# zulu_a7_1.net
KiCad netlist of a schematic drawn in Altium Designer
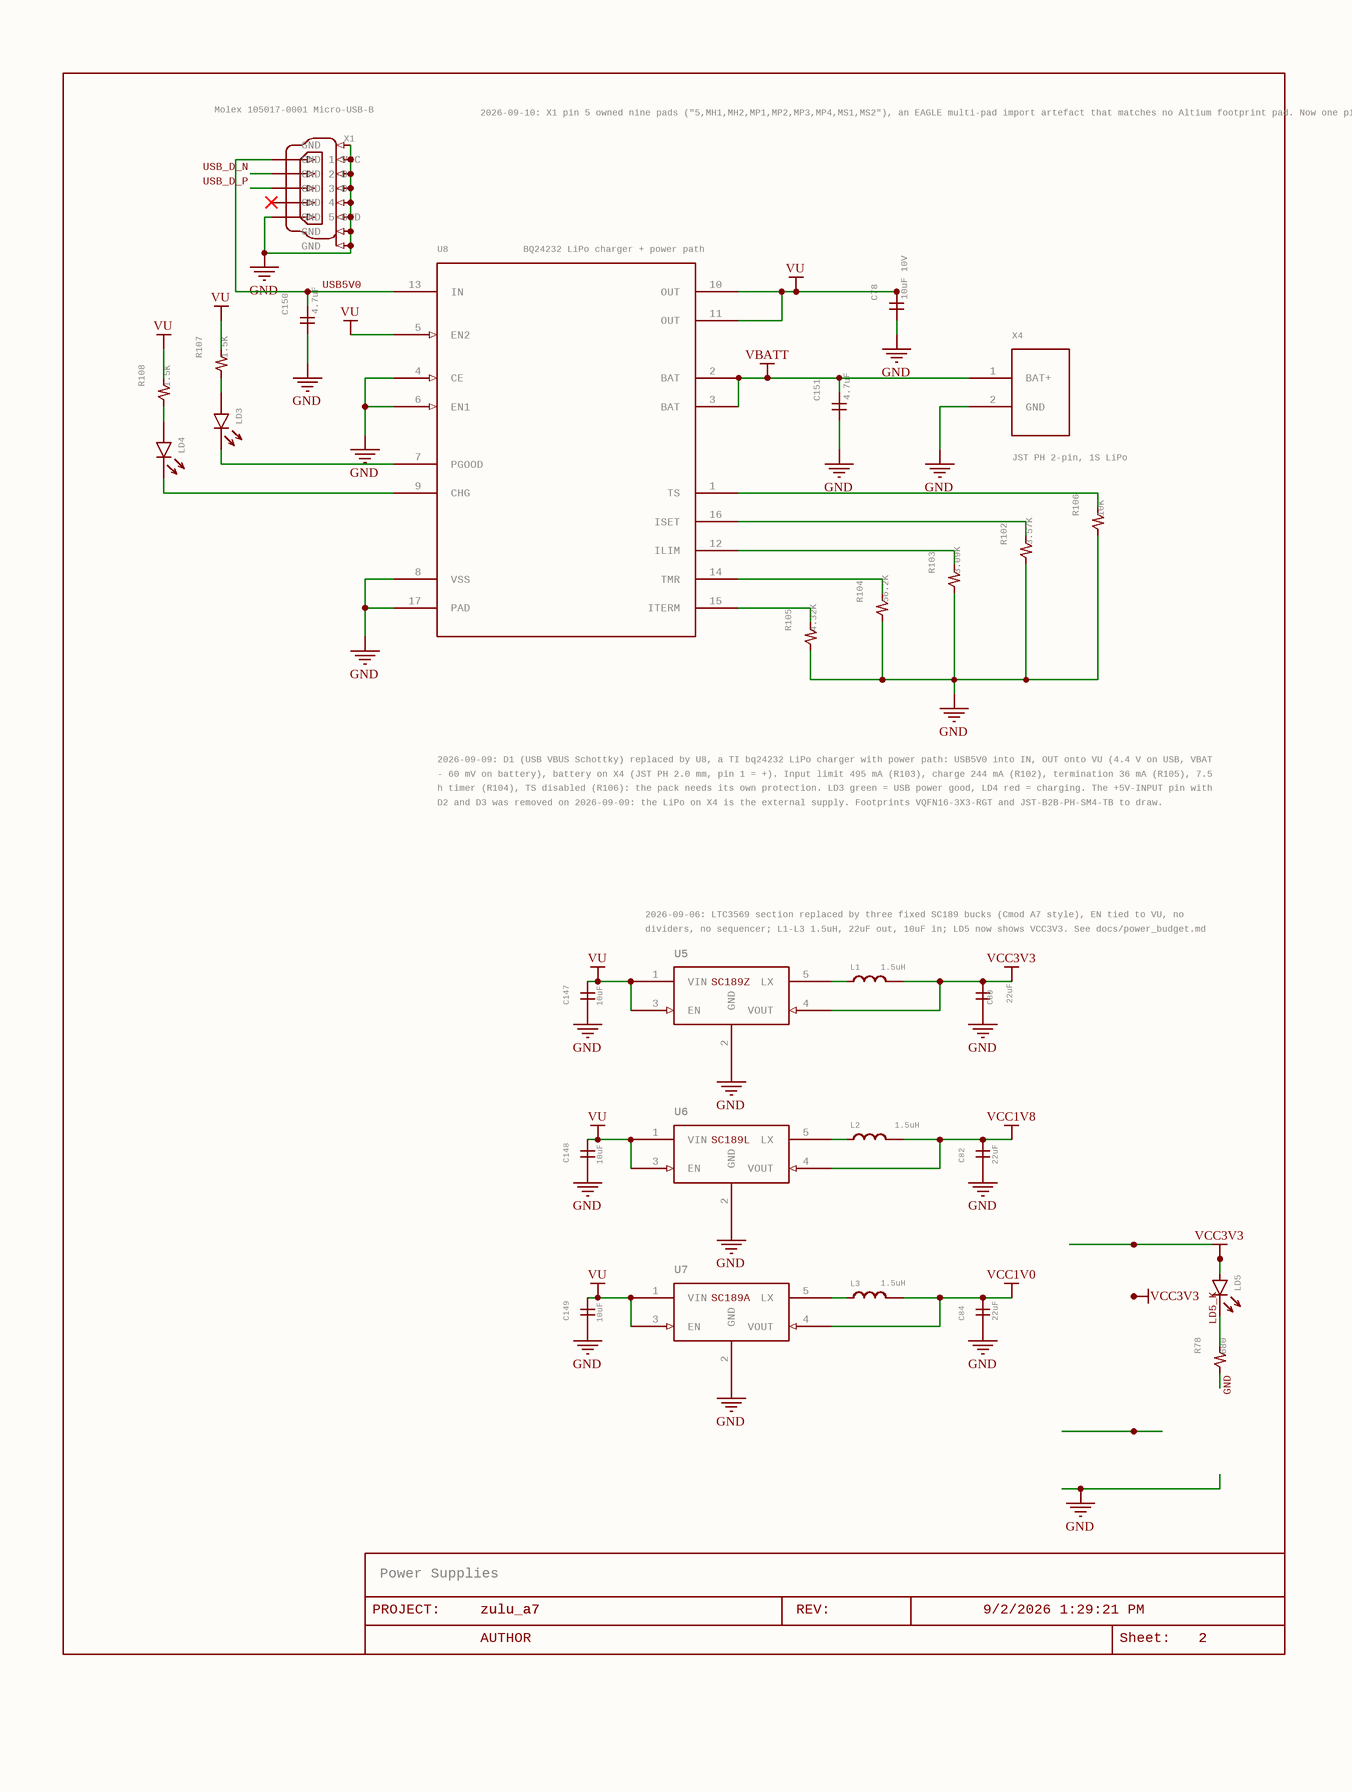
[diagram p0: zulu_a7_1.SchDoc]

(export (version "E")
  (design (tool "Eeschema 10.0.6"))
  (components
    (comp (ref "C78")
      (value "10uF 10V")
      (footprint "C0805")
      (description "CAPACITOR, generic non-polarized, horizontal pins")
      (fields (field (name "MANF") "Samsung"))
      (libsource (lib "rcl") (part "C-GENERICC0805"))
    )
    (comp (ref "C80")
      (value "22uF")
      (footprint "C0805")
      (description "CAPACITOR, generic non-polarized, horizontal pins")
      (fields (field (name "MANF") "Murata"))
      (libsource (lib "rcl") (part "C-GENERICC0805"))
    )
    (comp (ref "C82")
      (value "22uF")
      (footprint "C0603")
      (description "CAPACITOR, generic non-polarized, horizontal pins")
      (fields (field (name "MANF") "Samsung"))
      (libsource (lib "rcl") (part "C-GENERICC0603"))
    )
    (comp (ref "C84")
      (value "22uF")
      (footprint "C0603")
      (description "CAPACITOR, generic non-polarized, horizontal pins")
      (fields (field (name "MANF") "Samsung"))
      (libsource (lib "rcl") (part "C-GENERICC0603"))
    )
    (comp (ref "C147")
      (value "10uF")
      (footprint "C0805")
      (description "CAPACITOR, generic non-polarized, horizontal pins")
      (fields (field (name "MANF") "Samsung"))
      (libsource (lib "rcl") (part "C-GENERICC0805"))
    )
    (comp (ref "C148")
      (value "10uF")
      (footprint "C0805")
      (description "CAPACITOR, generic non-polarized, horizontal pins")
      (fields (field (name "MANF") "Samsung"))
      (libsource (lib "rcl") (part "C-GENERICC0805"))
    )
    (comp (ref "C149")
      (value "10uF")
      (footprint "C0805")
      (description "CAPACITOR, generic non-polarized, horizontal pins")
      (fields (field (name "MANF") "Samsung"))
      (libsource (lib "rcl") (part "C-GENERICC0805"))
    )
    (comp (ref "C150")
      (value "4.7uF")
      (footprint "C0603")
      (description "CAPACITOR, generic non-polarized, horizontal pins")
      (fields (field (name "MANF") "Murata"))
      (libsource (lib "rcl") (part "C-GENERICC0603"))
    )
    (comp (ref "C151")
      (value "4.7uF")
      (footprint "C0603")
      (description "CAPACITOR, generic non-polarized, horizontal pins")
      (fields (field (name "MANF") "Murata"))
      (libsource (lib "rcl") (part "C-GENERICC0603"))
    )
    (comp (ref "FRAME5")
      (value "DOCFIELD")
      (description "DOCUMENT FIELD")
      (fields
        (field (name "LAST_DATE_TIME") "9/2/2026 1:29:21 PM")
        (field (name "SHEET") "Sheet:")
        (field (name "SHEET_1") "2")
        (field (name "REV") "REV:")
        (field (name "PROJECT") "PROJECT:")
        (field (name "DRAWING_NAME") "zulu_a7")
        (field (name "AUTHOR") "AUTHOR")
        (field (name "DRAWING_NAME_1") "zulu_a7")
        (field (name "SHEET_2") "2")
        (field (name "LIBRARYNAME") "ctambe")
      )
      (libsource (lib "ctambe") (part "DOCFIELD"))
    )
    (comp (ref "L1")
      (value "1.5uH")
      (footprint "IND2520")
      (description "INDUCTOR, generic power inductor")
      (fields (field (name "MANF") "Murata") (field (name "LIBRARYNAME") "ctambe"))
      (libsource (lib "ctambe") (part "INDUCTOR-2520"))
    )
    (comp (ref "L2")
      (value "1.5uH")
      (footprint "IND2520")
      (description "INDUCTOR, generic power inductor")
      (fields (field (name "MANF") "Murata") (field (name "LIBRARYNAME") "ctambe"))
      (libsource (lib "ctambe") (part "INDUCTOR-2520"))
    )
    (comp (ref "L3")
      (value "1.5uH")
      (footprint "IND2520")
      (description "INDUCTOR, generic power inductor")
      (fields (field (name "MANF") "Murata") (field (name "LIBRARYNAME") "ctambe"))
      (libsource (lib "ctambe") (part "INDUCTOR-2520"))
    )
    (comp (ref "LD3")
      (value "green")
      (footprint "LED0603")
      (description "LED")
      (fields (field (name "MANF") "Lite-On") (field (name "LIBRARYNAME") "ctambe"))
      (libsource (lib "ctambe") (part "LED"))
    )
    (comp (ref "LD4")
      (value "red")
      (footprint "LED0603")
      (description "LED")
      (fields (field (name "MANF") "Lite-On") (field (name "LIBRARYNAME") "ctambe"))
      (libsource (lib "ctambe") (part "LED"))
    )
    (comp (ref "LD5")
      (value "green")
      (footprint "LED0603")
      (description "LED")
      (fields (field (name "MANF") "Lite-On") (field (name "LIBRARYNAME") "ctambe"))
      (libsource (lib "ctambe") (part "LED"))
    )
    (comp (ref "R78")
      (value "680")
      (footprint "R0402")
      (description "RESISTOR, American symbol, small 2-zigzag variant (sheet 2 only)")
      (fields (field (name "MANF") "Yageo"))
      (libsource (lib "rcl") (part "R-US_SMALLR0402"))
    )
    (comp (ref "R102")
      (value "3.57K")
      (footprint "R0402")
      (description "RESISTOR, American symbol, small 2-zigzag variant (sheet 2 only)")
      (fields (field (name "MANF") "Yageo"))
      (libsource (lib "rcl") (part "R-US_SMALLR0402"))
    )
    (comp (ref "R103")
      (value "3.09K")
      (footprint "R0402")
      (description "RESISTOR, American symbol, small 2-zigzag variant (sheet 2 only)")
      (fields (field (name "MANF") "Yageo"))
      (libsource (lib "rcl") (part "R-US_SMALLR0402"))
    )
    (comp (ref "R104")
      (value "56.2K")
      (footprint "R0402")
      (description "RESISTOR, American symbol, small 2-zigzag variant (sheet 2 only)")
      (fields (field (name "MANF") "Yageo"))
      (libsource (lib "rcl") (part "R-US_SMALLR0402"))
    )
    (comp (ref "R105")
      (value "4.32K")
      (footprint "R0402")
      (description "RESISTOR, American symbol, small 2-zigzag variant (sheet 2 only)")
      (fields (field (name "MANF") "Yageo"))
      (libsource (lib "rcl") (part "R-US_SMALLR0402"))
    )
    (comp (ref "R106")
      (value "10K")
      (footprint "R0402")
      (description "RESISTOR, American symbol, small 2-zigzag variant (sheet 2 only)")
      (fields (field (name "MANF") "Yageo"))
      (libsource (lib "rcl") (part "R-US_SMALLR0402"))
    )
    (comp (ref "R107")
      (value "1.5K")
      (footprint "R0402")
      (description "RESISTOR, American symbol, small 2-zigzag variant (sheet 2 only)")
      (fields (field (name "MANF") "Yageo"))
      (libsource (lib "rcl") (part "R-US_SMALLR0402"))
    )
    (comp (ref "R108")
      (value "1.5K")
      (footprint "R0402")
      (description "RESISTOR, American symbol, small 2-zigzag variant (sheet 2 only)")
      (fields (field (name "MANF") "Yageo"))
      (libsource (lib "rcl") (part "R-US_SMALLR0402"))
    )
    (comp (ref "U5")
      (value "SC189ZSKTRT")
      (footprint "SOT23-5")
      (description "1.5A 2.5MHz synchronous buck, fixed output (Semtech SC189)")
      (fields (field (name "PARTNAME") "SC189Z") (field (name "MANF") "Semtech"))
      (libsource (lib "ctambe") (part "SC189-SOT23-5"))
    )
    (comp (ref "U6")
      (value "SC189LSKTRT")
      (footprint "SOT23-5")
      (description "1.5A 2.5MHz synchronous buck, fixed output (Semtech SC189)")
      (fields (field (name "PARTNAME") "SC189L") (field (name "MANF") "Semtech"))
      (libsource (lib "ctambe") (part "SC189-SOT23-5"))
    )
    (comp (ref "U7")
      (value "SC189ASKTRT")
      (footprint "SOT23-5")
      (description "1.5A 2.5MHz synchronous buck, fixed output (Semtech SC189)")
      (fields (field (name "PARTNAME") "SC189A") (field (name "MANF") "Semtech"))
      (libsource (lib "ctambe") (part "SC189-SOT23-5"))
    )
    (comp (ref "U8")
      (value "BQ24232 LiPo charger + power path")
      (footprint "VQFN16-3X3-RGT")
      (fields (field (name "MANF") "Texas Instruments") (field (name "LIBRARYNAME") "ctambe"))
      (libsource (lib "ctambe") (part "BQ24232-RGT16"))
    )
    (comp (ref "X1")
      (value "Molex 105017-0001 Micro-USB-B")
      (footprint "MOLEX-105017-0001")
      (description "MINI USB Connector   Source: http://www.hirose.co.jp/cataloge_hp/e24000019.pdf")
      (fields (field (name "MANF") "Molex") (field (name "LIBRARYNAME") "ctambe"))
      (libsource (lib "ctambe") (part "MINI-USB-105017-0001"))
    )
    (comp (ref "X4")
      (value "JST PH 2-pin, 1S LiPo")
      (footprint "JST-B2B-PH-SM4-TB")
      (description "JST PH 2.0 mm 2-pin top-entry SMT header, LiPo battery input")
      (fields (field (name "MANF") "JST") (field (name "LIBRARYNAME") "ctambe"))
      (libsource (lib "ctambe") (part "JST-B2B-PH-SM4-TB"))
    )
  )
  (nets
    (net (code "1") (name "/LD5_K") (class "Default")
      (node (ref "LD5") (pin "K") (pinfunction "K_K") (pintype "passive"))
      (node (ref "R78") (pin "2") (pinfunction "2_2") (pintype "passive"))
    )
    (net (code "2") (name "/USB5V0") (class "Default")
      (node (ref "C150") (pin "2") (pinfunction "2_2") (pintype "passive"))
      (node (ref "U8") (pin "13") (pinfunction "IN_13") (pintype "power_in"))
      (node (ref "X1") (pin "1") (pinfunction "1-VCC_1") (pintype "input"))
    )
    (net (code "3") (name "/USB_D_N") (class "Default")
      (node (ref "X1") (pin "2") (pinfunction "2-D-_2") (pintype "input"))
    )
    (net (code "4") (name "/USB_D_P") (class "Default")
      (node (ref "X1") (pin "3") (pinfunction "3-D+_3") (pintype "input"))
    )
    (net (code "5") (name "GND") (class "Default")
      (node (ref "C147") (pin "1") (pinfunction "1_1") (pintype "passive"))
      (node (ref "C148") (pin "1") (pinfunction "1_1") (pintype "passive"))
      (node (ref "C149") (pin "1") (pinfunction "1_1") (pintype "passive"))
      (node (ref "C150") (pin "1") (pinfunction "1_1") (pintype "passive"))
      (node (ref "C151") (pin "1") (pinfunction "1_1") (pintype "passive"))
      (node (ref "C78") (pin "1") (pinfunction "1_1") (pintype "passive"))
      (node (ref "C80") (pin "1") (pinfunction "1_1") (pintype "passive"))
      (node (ref "C82") (pin "1") (pinfunction "1_1") (pintype "passive"))
      (node (ref "C84") (pin "1") (pinfunction "1_1") (pintype "passive"))
      (node (ref "R102") (pin "1") (pinfunction "1_1") (pintype "passive"))
      (node (ref "R103") (pin "1") (pinfunction "1_1") (pintype "passive"))
      (node (ref "R104") (pin "1") (pinfunction "1_1") (pintype "passive"))
      (node (ref "R105") (pin "1") (pinfunction "1_1") (pintype "passive"))
      (node (ref "R106") (pin "1") (pinfunction "1_1") (pintype "passive"))
      (node (ref "R78") (pin "1") (pinfunction "1_1") (pintype "passive"))
      (node (ref "U5") (pin "2") (pinfunction "GND_2") (pintype "power_in"))
      (node (ref "U6") (pin "2") (pinfunction "GND_2") (pintype "power_in"))
      (node (ref "U7") (pin "2") (pinfunction "GND_2") (pintype "power_in"))
      (node (ref "U8") (pin "17") (pinfunction "PAD_17") (pintype "power_in"))
      (node (ref "U8") (pin "4") (pinfunction "CE_4") (pintype "input"))
      (node (ref "U8") (pin "6") (pinfunction "EN1_6") (pintype "input"))
      (node (ref "U8") (pin "8") (pinfunction "VSS_8") (pintype "power_in"))
      (node (ref "X1") (pin "5") (pinfunction "5-GND_5") (pintype "input"))
      (node (ref "X1") (pin "MH1") (pinfunction "GND_MH1") (pintype "input"))
      (node (ref "X1") (pin "MH2") (pinfunction "GND_MH2") (pintype "input"))
      (node (ref "X1") (pin "MP1") (pinfunction "GND_MP1") (pintype "input"))
      (node (ref "X1") (pin "MP2") (pinfunction "GND_MP2") (pintype "input"))
      (node (ref "X1") (pin "MP3") (pinfunction "GND_MP3") (pintype "input"))
      (node (ref "X1") (pin "MP4") (pinfunction "GND_MP4") (pintype "input"))
      (node (ref "X1") (pin "MS1") (pinfunction "GND_MS1") (pintype "input"))
      (node (ref "X1") (pin "MS2") (pinfunction "GND_MS2") (pintype "input"))
      (node (ref "X4") (pin "2") (pinfunction "GND_2") (pintype "passive"))
    )
    (net (code "6") (name "Net-(LD3-PadA)") (class "Default")
      (node (ref "LD3") (pin "A") (pinfunction "A_A") (pintype "passive"))
      (node (ref "R107") (pin "1") (pinfunction "1_1") (pintype "passive"))
    )
    (net (code "7") (name "Net-(LD4-PadA)") (class "Default")
      (node (ref "LD4") (pin "A") (pinfunction "A_A") (pintype "passive"))
      (node (ref "R108") (pin "1") (pinfunction "1_1") (pintype "passive"))
    )
    (net (code "8") (name "Net-(U5-LX)") (class "Default")
      (node (ref "L1") (pin "1") (pinfunction "1_1") (pintype "passive"))
      (node (ref "U5") (pin "5") (pinfunction "LX_5") (pintype "passive"))
    )
    (net (code "9") (name "Net-(U6-LX)") (class "Default")
      (node (ref "L2") (pin "1") (pinfunction "1_1") (pintype "passive"))
      (node (ref "U6") (pin "5") (pinfunction "LX_5") (pintype "passive"))
    )
    (net (code "10") (name "Net-(U7-LX)") (class "Default")
      (node (ref "L3") (pin "1") (pinfunction "1_1") (pintype "passive"))
      (node (ref "U7") (pin "5") (pinfunction "LX_5") (pintype "passive"))
    )
    (net (code "11") (name "Net-(U8-CHG)") (class "Default")
      (node (ref "LD4") (pin "K") (pinfunction "K_K") (pintype "passive"))
      (node (ref "U8") (pin "9") (pinfunction "CHG_9") (pintype "open_collector"))
    )
    (net (code "12") (name "Net-(U8-ILIM)") (class "Default")
      (node (ref "R103") (pin "2") (pinfunction "2_2") (pintype "passive"))
      (node (ref "U8") (pin "12") (pinfunction "ILIM_12") (pintype "passive"))
    )
    (net (code "13") (name "Net-(U8-ISET)") (class "Default")
      (node (ref "R102") (pin "2") (pinfunction "2_2") (pintype "passive"))
      (node (ref "U8") (pin "16") (pinfunction "ISET_16") (pintype "passive"))
    )
    (net (code "14") (name "Net-(U8-ITERM)") (class "Default")
      (node (ref "R105") (pin "2") (pinfunction "2_2") (pintype "passive"))
      (node (ref "U8") (pin "15") (pinfunction "ITERM_15") (pintype "passive"))
    )
    (net (code "15") (name "Net-(U8-PGOOD)") (class "Default")
      (node (ref "LD3") (pin "K") (pinfunction "K_K") (pintype "passive"))
      (node (ref "U8") (pin "7") (pinfunction "PGOOD_7") (pintype "open_collector"))
    )
    (net (code "16") (name "Net-(U8-TMR)") (class "Default")
      (node (ref "R104") (pin "2") (pinfunction "2_2") (pintype "passive"))
      (node (ref "U8") (pin "14") (pinfunction "TMR_14") (pintype "passive"))
    )
    (net (code "17") (name "Net-(U8-TS)") (class "Default")
      (node (ref "R106") (pin "2") (pinfunction "2_2") (pintype "passive"))
      (node (ref "U8") (pin "1") (pinfunction "TS_1") (pintype "passive"))
    )
    (net (code "18") (name "VBATT") (class "Default")
      (node (ref "C151") (pin "2") (pinfunction "2_2") (pintype "passive"))
      (node (ref "U8") (pin "2") (pinfunction "BAT_2") (pintype "power_in"))
      (node (ref "U8") (pin "3") (pinfunction "BAT_3") (pintype "power_in"))
      (node (ref "X4") (pin "1") (pinfunction "BAT+_1") (pintype "passive"))
    )
    (net (code "19") (name "VCC1V0") (class "Default")
      (node (ref "C84") (pin "2") (pinfunction "2_2") (pintype "passive"))
      (node (ref "L3") (pin "2") (pinfunction "2_2") (pintype "passive"))
      (node (ref "U7") (pin "4") (pinfunction "VOUT_4") (pintype "input"))
    )
    (net (code "20") (name "VCC1V8") (class "Default")
      (node (ref "C82") (pin "2") (pinfunction "2_2") (pintype "passive"))
      (node (ref "L2") (pin "2") (pinfunction "2_2") (pintype "passive"))
      (node (ref "U6") (pin "4") (pinfunction "VOUT_4") (pintype "input"))
    )
    (net (code "21") (name "VCC3V3") (class "Default")
      (node (ref "C80") (pin "2") (pinfunction "2_2") (pintype "passive"))
      (node (ref "L1") (pin "2") (pinfunction "2_2") (pintype "passive"))
      (node (ref "LD5") (pin "A") (pinfunction "A_A") (pintype "passive"))
      (node (ref "U5") (pin "4") (pinfunction "VOUT_4") (pintype "input"))
    )
    (net (code "22") (name "VU") (class "Default")
      (node (ref "C147") (pin "2") (pinfunction "2_2") (pintype "passive"))
      (node (ref "C148") (pin "2") (pinfunction "2_2") (pintype "passive"))
      (node (ref "C149") (pin "2") (pinfunction "2_2") (pintype "passive"))
      (node (ref "C78") (pin "2") (pinfunction "2_2") (pintype "passive"))
      (node (ref "R107") (pin "2") (pinfunction "2_2") (pintype "passive"))
      (node (ref "R108") (pin "2") (pinfunction "2_2") (pintype "passive"))
      (node (ref "U5") (pin "1") (pinfunction "VIN_1") (pintype "power_in"))
      (node (ref "U5") (pin "3") (pinfunction "EN_3") (pintype "input"))
      (node (ref "U6") (pin "1") (pinfunction "VIN_1") (pintype "power_in"))
      (node (ref "U6") (pin "3") (pinfunction "EN_3") (pintype "input"))
      (node (ref "U7") (pin "1") (pinfunction "VIN_1") (pintype "power_in"))
      (node (ref "U7") (pin "3") (pinfunction "EN_3") (pintype "input"))
      (node (ref "U8") (pin "10") (pinfunction "OUT_10") (pintype "power_in"))
      (node (ref "U8") (pin "11") (pinfunction "OUT_11") (pintype "power_in"))
      (node (ref "U8") (pin "5") (pinfunction "EN2_5") (pintype "input"))
    )
    (net (code "23") (name "unconnected-(X1-Pad4)") (class "Default")
      (node (ref "X1") (pin "4") (pinfunction "4_4") (pintype "input+no_connect"))
    )
  )
)
